# bikealarm.net
KiCad netlist of a schematic drawn in EAGLE
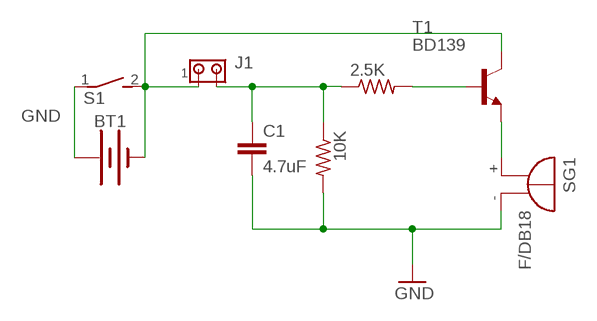
[diagram p0: schematic, sheet 1]

(export (version "E")
  (design (tool "Eeschema 10.0.6"))
  (components
    (comp (ref "2.5K")
      (value "R-US_0204/7")
      (footprint "eagle-import:0204_7")
      (libsource (lib "eagle-import") (part "R-US_0204/7"))
    )
    (comp (ref "10K")
      (value "R-US_0204/7")
      (footprint "eagle-import:0204_7")
      (libsource (lib "eagle-import") (part "R-US_0204/7"))
    )
    (comp (ref "BT1")
      (value "BATTERY-AA-HOLDER_KIT")
      (footprint "eagle-import:BATTERY-AA-HOLDER-KIT")
      (libsource (lib "eagle-import") (part "BATTERY-AA-HOLDER_KIT"))
    )
    (comp (ref "C1")
      (value "4.7uF")
      (footprint "eagle-import:C025-030X050")
      (libsource (lib "eagle-import") (part "C-EU025-030X050"))
    )
    (comp (ref "J1")
      (value "MTA02-156")
      (footprint "eagle-import:1X2MTA")
      (libsource (lib "eagle-import") (part "MTA02-156"))
    )
    (comp (ref "S1")
      (value "DS01E")
      (footprint "eagle-import:DS-01")
      (libsource (lib "eagle-import") (part "DS01E"))
    )
    (comp (ref "SG1")
      (value "F/DB18")
      (footprint "eagle-import:F_DB18")
      (libsource (lib "eagle-import") (part "F/DB18"))
    )
    (comp (ref "T1")
      (value "BD139")
      (footprint "eagle-import:TO126")
      (libsource (lib "eagle-import") (part "BD139"))
    )
  )
  (nets
    (net (code "1") (name "GND") (class "Default")
      (node (ref "10K") (pin "2") (pinfunction "2_2") (pintype "passive"))
      (node (ref "BT1") (pin "P") (pinfunction "+_P") (pintype "power_in"))
      (node (ref "C1") (pin "2") (pinfunction "2_2") (pintype "passive"))
      (node (ref "S1") (pin "1") (pinfunction "1_1") (pintype "passive"))
      (node (ref "SG1") (pin "-") (pinfunction "-_-") (pintype "passive"))
    )
    (net (code "2") (name "Net-(10K-Pad1)") (class "Default")
      (node (ref "10K") (pin "1") (pinfunction "1_1") (pintype "passive"))
      (node (ref "2.5K") (pin "1") (pinfunction "1_1") (pintype "passive"))
      (node (ref "C1") (pin "1") (pinfunction "1_1") (pintype "passive"))
      (node (ref "J1") (pin "2") (pinfunction "2_2") (pintype "passive"))
    )
    (net (code "3") (name "Net-(BT1--)") (class "Default")
      (node (ref "BT1") (pin "N") (pinfunction "-_N") (pintype "power_in"))
      (node (ref "J1") (pin "1") (pinfunction "1_1") (pintype "passive"))
      (node (ref "S1") (pin "2") (pinfunction "2_2") (pintype "passive"))
      (node (ref "T1") (pin "2") (pinfunction "C_2") (pintype "passive"))
    )
    (net (code "4") (name "Net-(T1-B)") (class "Default")
      (node (ref "2.5K") (pin "2") (pinfunction "2_2") (pintype "passive"))
      (node (ref "T1") (pin "3") (pinfunction "B_3") (pintype "passive"))
    )
    (net (code "5") (name "Net-(T1-E)") (class "Default")
      (node (ref "SG1") (pin "+") (pinfunction "+_+") (pintype "passive"))
      (node (ref "T1") (pin "1") (pinfunction "E_1") (pintype "passive"))
    )
  )
)
